# rtc.net
KiCad netlist of a schematic drawn in EAGLE
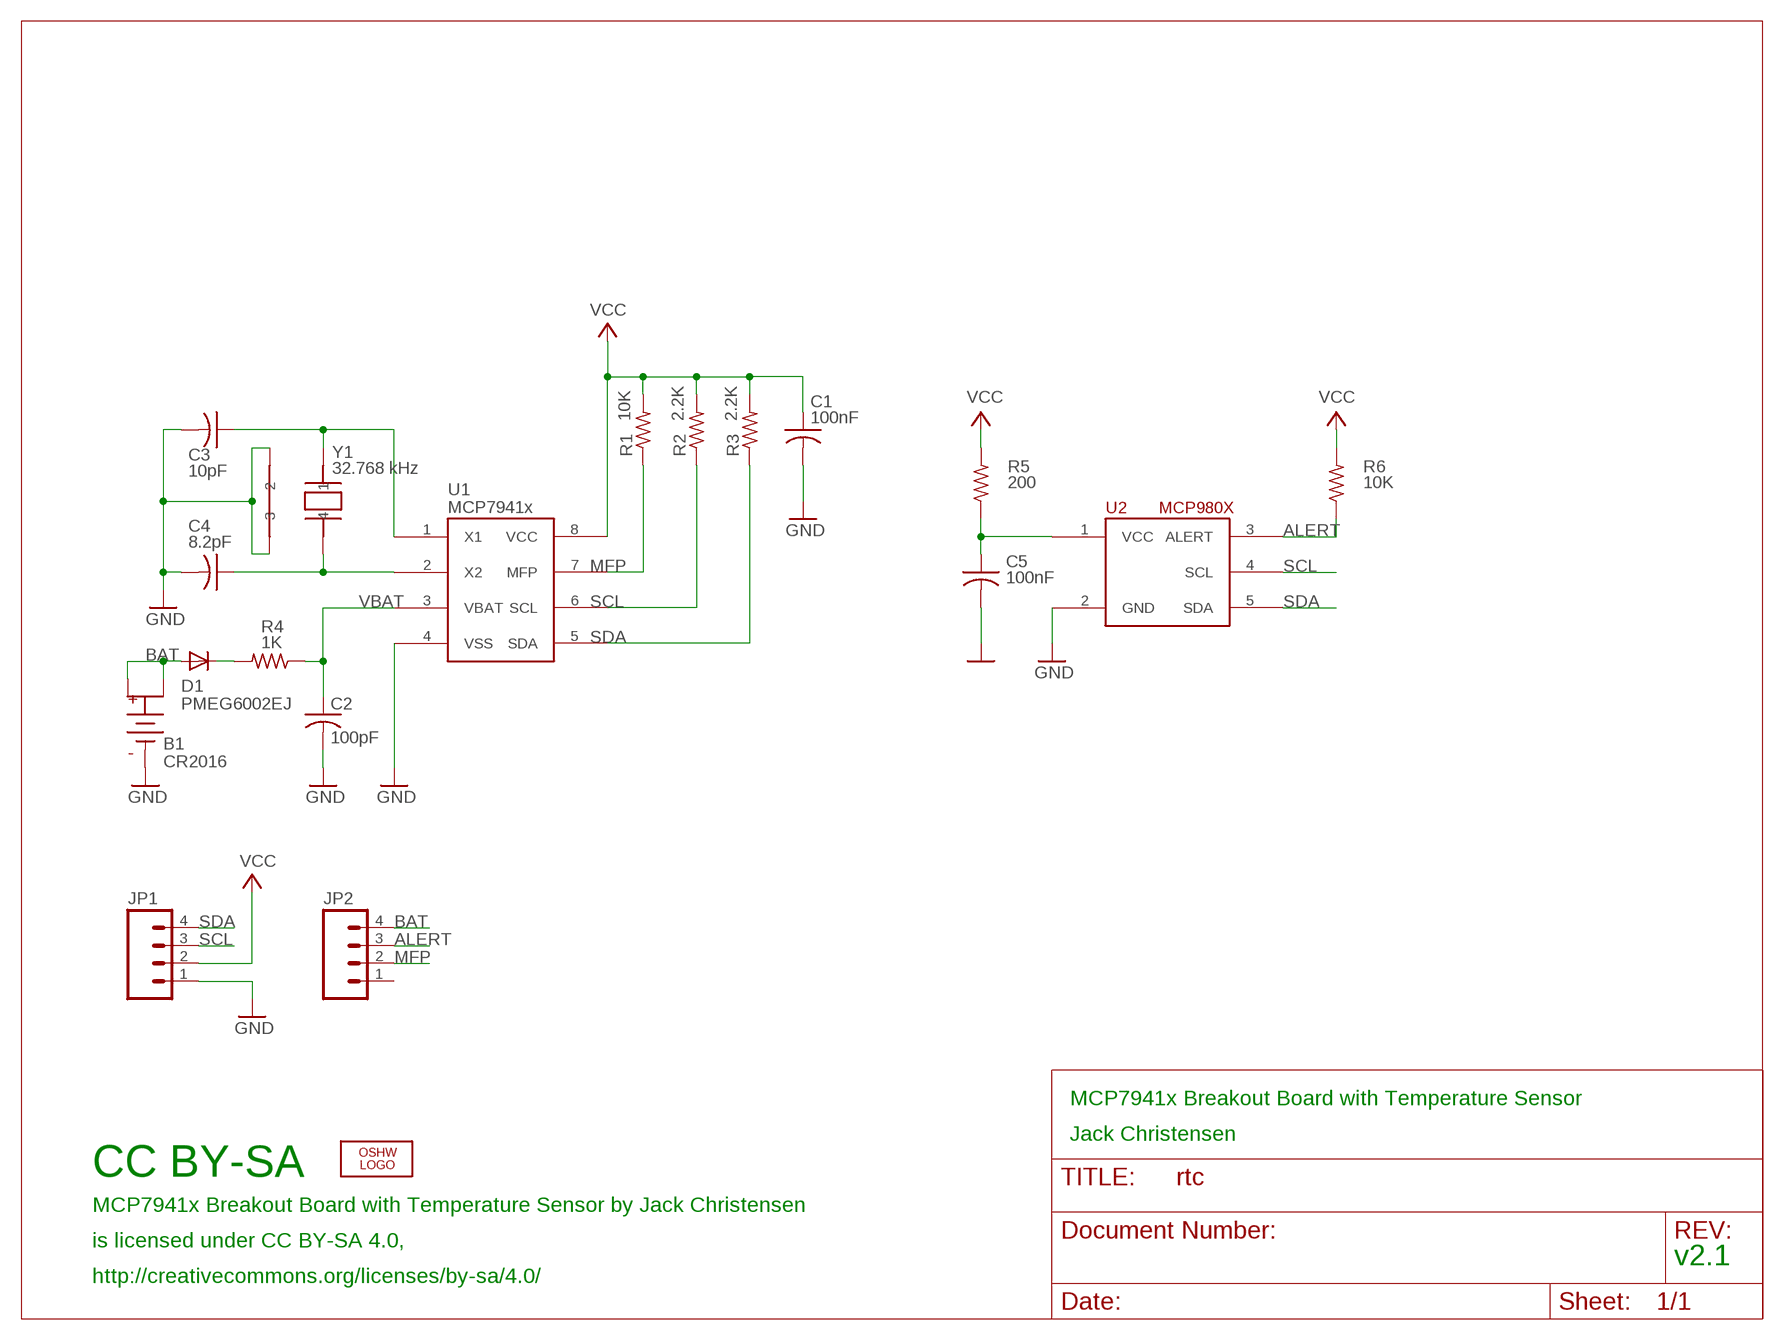
[diagram p0: schematic, sheet 1]

(export (version "E")
  (design (tool "Eeschema 10.0.6"))
  (components
    (comp (ref "B1")
      (value "CR2016")
      (footprint "eagle-import:BAT-HLD-002-SMT")
      (libsource (lib "eagle-import") (part "COIN-CELL-2016-SMT"))
    )
    (comp (ref "C1")
      (value "100nF")
      (footprint "eagle-import:M0805")
      (libsource (lib "eagle-import") (part "C-USM0805"))
    )
    (comp (ref "C2")
      (value "100pF")
      (footprint "eagle-import:M0805")
      (libsource (lib "eagle-import") (part "C-USM0805"))
    )
    (comp (ref "C3")
      (value "10pF")
      (footprint "eagle-import:M0805")
      (libsource (lib "eagle-import") (part "C-USM0805"))
    )
    (comp (ref "C4")
      (value "8.2pF")
      (footprint "eagle-import:M0805")
      (libsource (lib "eagle-import") (part "C-USM0805"))
    )
    (comp (ref "C5")
      (value "100nF")
      (footprint "eagle-import:M0805")
      (libsource (lib "eagle-import") (part "C-USM0805"))
    )
    (comp (ref "D1")
      (value "PMEG6002EJ")
      (footprint "eagle-import:SOD-323F-A")
      (libsource (lib "eagle-import") (part "DIODESOD-323F-A"))
    )
    (comp (ref "JP1")
      (value "M04LOCK")
      (footprint "eagle-import:1X04_LOCK")
      (libsource (lib "eagle-import") (part "M04LOCK"))
    )
    (comp (ref "JP2")
      (value "M04LOCK")
      (footprint "eagle-import:1X04_LOCK")
      (libsource (lib "eagle-import") (part "M04LOCK"))
    )
    (comp (ref "LOGO2")
      (value "OSHW_LOGO_8MILX0150-NT")
      (footprint "eagle-import:OSHW_8X150_NOTEXT")
      (libsource (lib "eagle-import") (part "OSHW_LOGO_8MILX0150-NT"))
    )
    (comp (ref "R1")
      (value "10K")
      (footprint "eagle-import:M0805")
      (libsource (lib "eagle-import") (part "R-US_M0805"))
    )
    (comp (ref "R2")
      (value "2.2K")
      (footprint "eagle-import:M0805")
      (libsource (lib "eagle-import") (part "R-US_M0805"))
    )
    (comp (ref "R3")
      (value "2.2K")
      (footprint "eagle-import:M0805")
      (libsource (lib "eagle-import") (part "R-US_M0805"))
    )
    (comp (ref "R4")
      (value "1K")
      (footprint "eagle-import:M0805")
      (libsource (lib "eagle-import") (part "R-US_M0805"))
    )
    (comp (ref "R5")
      (value "200")
      (footprint "eagle-import:M0805")
      (libsource (lib "eagle-import") (part "R-US_M0805"))
    )
    (comp (ref "R6")
      (value "10K")
      (footprint "eagle-import:M0805")
      (libsource (lib "eagle-import") (part "R-US_M0805"))
    )
    (comp (ref "U1")
      (value "MCP7941x")
      (footprint "eagle-import:MSOP8")
      (libsource (lib "eagle-import") (part "MCP7941XMSOP8"))
    )
    (comp (ref "U2")
      (value "MCP980X")
      (footprint "eagle-import:SOT23-5L")
      (libsource (lib "eagle-import") (part "MCP980X"))
    )
    (comp (ref "Y1")
      (value "32.768 kHz")
      (footprint "eagle-import:CRYSTAL-CITIZEN-CM2XXC")
      (libsource (lib "eagle-import") (part "CRYSTAL-CITIZEN-CM2XXC"))
    )
  )
  (nets
    (net (code "1") (name "/ALERT") (class "Default")
      (node (ref "JP2") (pin "3") (pinfunction "3_3") (pintype "passive"))
      (node (ref "R6") (pin "1") (pinfunction "1_1") (pintype "passive"))
      (node (ref "U2") (pin "3") (pinfunction "ALERT_3") (pintype "passive"))
    )
    (net (code "2") (name "/BAT") (class "Default")
      (node (ref "B1") (pin "POS1") (pinfunction "POS1_POS1") (pintype "passive"))
      (node (ref "B1") (pin "POS2") (pinfunction "POS2_POS2") (pintype "passive"))
      (node (ref "D1") (pin "A") (pinfunction "A_A") (pintype "passive"))
      (node (ref "JP2") (pin "4") (pinfunction "4_4") (pintype "passive"))
    )
    (net (code "3") (name "/MFP") (class "Default")
      (node (ref "JP2") (pin "2") (pinfunction "2_2") (pintype "passive"))
      (node (ref "R1") (pin "1") (pinfunction "1_1") (pintype "passive"))
      (node (ref "U1") (pin "7") (pinfunction "MFP_7") (pintype "passive"))
    )
    (net (code "4") (name "/SCL") (class "Default")
      (node (ref "JP1") (pin "3") (pinfunction "3_3") (pintype "passive"))
      (node (ref "R2") (pin "1") (pinfunction "1_1") (pintype "passive"))
      (node (ref "U1") (pin "6") (pinfunction "SCL_6") (pintype "passive"))
      (node (ref "U2") (pin "4") (pinfunction "SCL_4") (pintype "passive"))
    )
    (net (code "5") (name "/SDA") (class "Default")
      (node (ref "JP1") (pin "4") (pinfunction "4_4") (pintype "passive"))
      (node (ref "R3") (pin "1") (pinfunction "1_1") (pintype "passive"))
      (node (ref "U1") (pin "5") (pinfunction "SDA_5") (pintype "passive"))
      (node (ref "U2") (pin "5") (pinfunction "SDA_5") (pintype "passive"))
    )
    (net (code "6") (name "/VBAT") (class "Default")
      (node (ref "C2") (pin "1") (pinfunction "1_1") (pintype "passive"))
      (node (ref "R4") (pin "1") (pinfunction "1_1") (pintype "passive"))
      (node (ref "U1") (pin "3") (pinfunction "VBAT_3") (pintype "passive"))
    )
    (net (code "7") (name "GND") (class "Default")
      (node (ref "B1") (pin "NEG") (pinfunction "B-_NEG") (pintype "passive"))
      (node (ref "C1") (pin "2") (pinfunction "2_2") (pintype "passive"))
      (node (ref "C2") (pin "2") (pinfunction "2_2") (pintype "passive"))
      (node (ref "C3") (pin "2") (pinfunction "2_2") (pintype "passive"))
      (node (ref "C4") (pin "2") (pinfunction "2_2") (pintype "passive"))
      (node (ref "C5") (pin "2") (pinfunction "2_2") (pintype "passive"))
      (node (ref "JP1") (pin "1") (pinfunction "1_1") (pintype "passive"))
      (node (ref "U1") (pin "4") (pinfunction "VSS_4") (pintype "passive"))
      (node (ref "U2") (pin "2") (pinfunction "GND_2") (pintype "passive"))
      (node (ref "Y1") (pin "P$2") (pinfunction "2_P$2") (pintype "passive"))
      (node (ref "Y1") (pin "P$3") (pinfunction "3_P$3") (pintype "passive"))
    )
    (net (code "8") (name "Net-(D1-PadK)") (class "Default")
      (node (ref "D1") (pin "K") (pinfunction "K_K") (pintype "passive"))
      (node (ref "R4") (pin "2") (pinfunction "2_2") (pintype "passive"))
    )
    (net (code "9") (name "Net-(U1-X1)") (class "Default")
      (node (ref "C3") (pin "1") (pinfunction "1_1") (pintype "passive"))
      (node (ref "U1") (pin "1") (pinfunction "X1_1") (pintype "passive"))
      (node (ref "Y1") (pin "P$1") (pinfunction "1_P$1") (pintype "passive"))
    )
    (net (code "10") (name "Net-(U1-X2)") (class "Default")
      (node (ref "C4") (pin "1") (pinfunction "1_1") (pintype "passive"))
      (node (ref "U1") (pin "2") (pinfunction "X2_2") (pintype "passive"))
      (node (ref "Y1") (pin "P$4") (pinfunction "4_P$4") (pintype "passive"))
    )
    (net (code "11") (name "Net-(U2-VCC)") (class "Default")
      (node (ref "C5") (pin "1") (pinfunction "1_1") (pintype "passive"))
      (node (ref "R5") (pin "1") (pinfunction "1_1") (pintype "passive"))
      (node (ref "U2") (pin "1") (pinfunction "VCC_1") (pintype "passive"))
    )
    (net (code "12") (name "VCC") (class "Default")
      (node (ref "C1") (pin "1") (pinfunction "1_1") (pintype "passive"))
      (node (ref "JP1") (pin "2") (pinfunction "2_2") (pintype "passive"))
      (node (ref "R1") (pin "2") (pinfunction "2_2") (pintype "passive"))
      (node (ref "R2") (pin "2") (pinfunction "2_2") (pintype "passive"))
      (node (ref "R3") (pin "2") (pinfunction "2_2") (pintype "passive"))
      (node (ref "R5") (pin "2") (pinfunction "2_2") (pintype "passive"))
      (node (ref "R6") (pin "2") (pinfunction "2_2") (pintype "passive"))
      (node (ref "U1") (pin "8") (pinfunction "VCC_8") (pintype "passive"))
    )
    (net (code "13") (name "unconnected-(JP2-Pad1)") (class "Default")
      (node (ref "JP2") (pin "1") (pinfunction "1_1") (pintype "passive"))
    )
  )
)
